# decoupling.net
KiCad netlist of a schematic drawn in Altium Designer
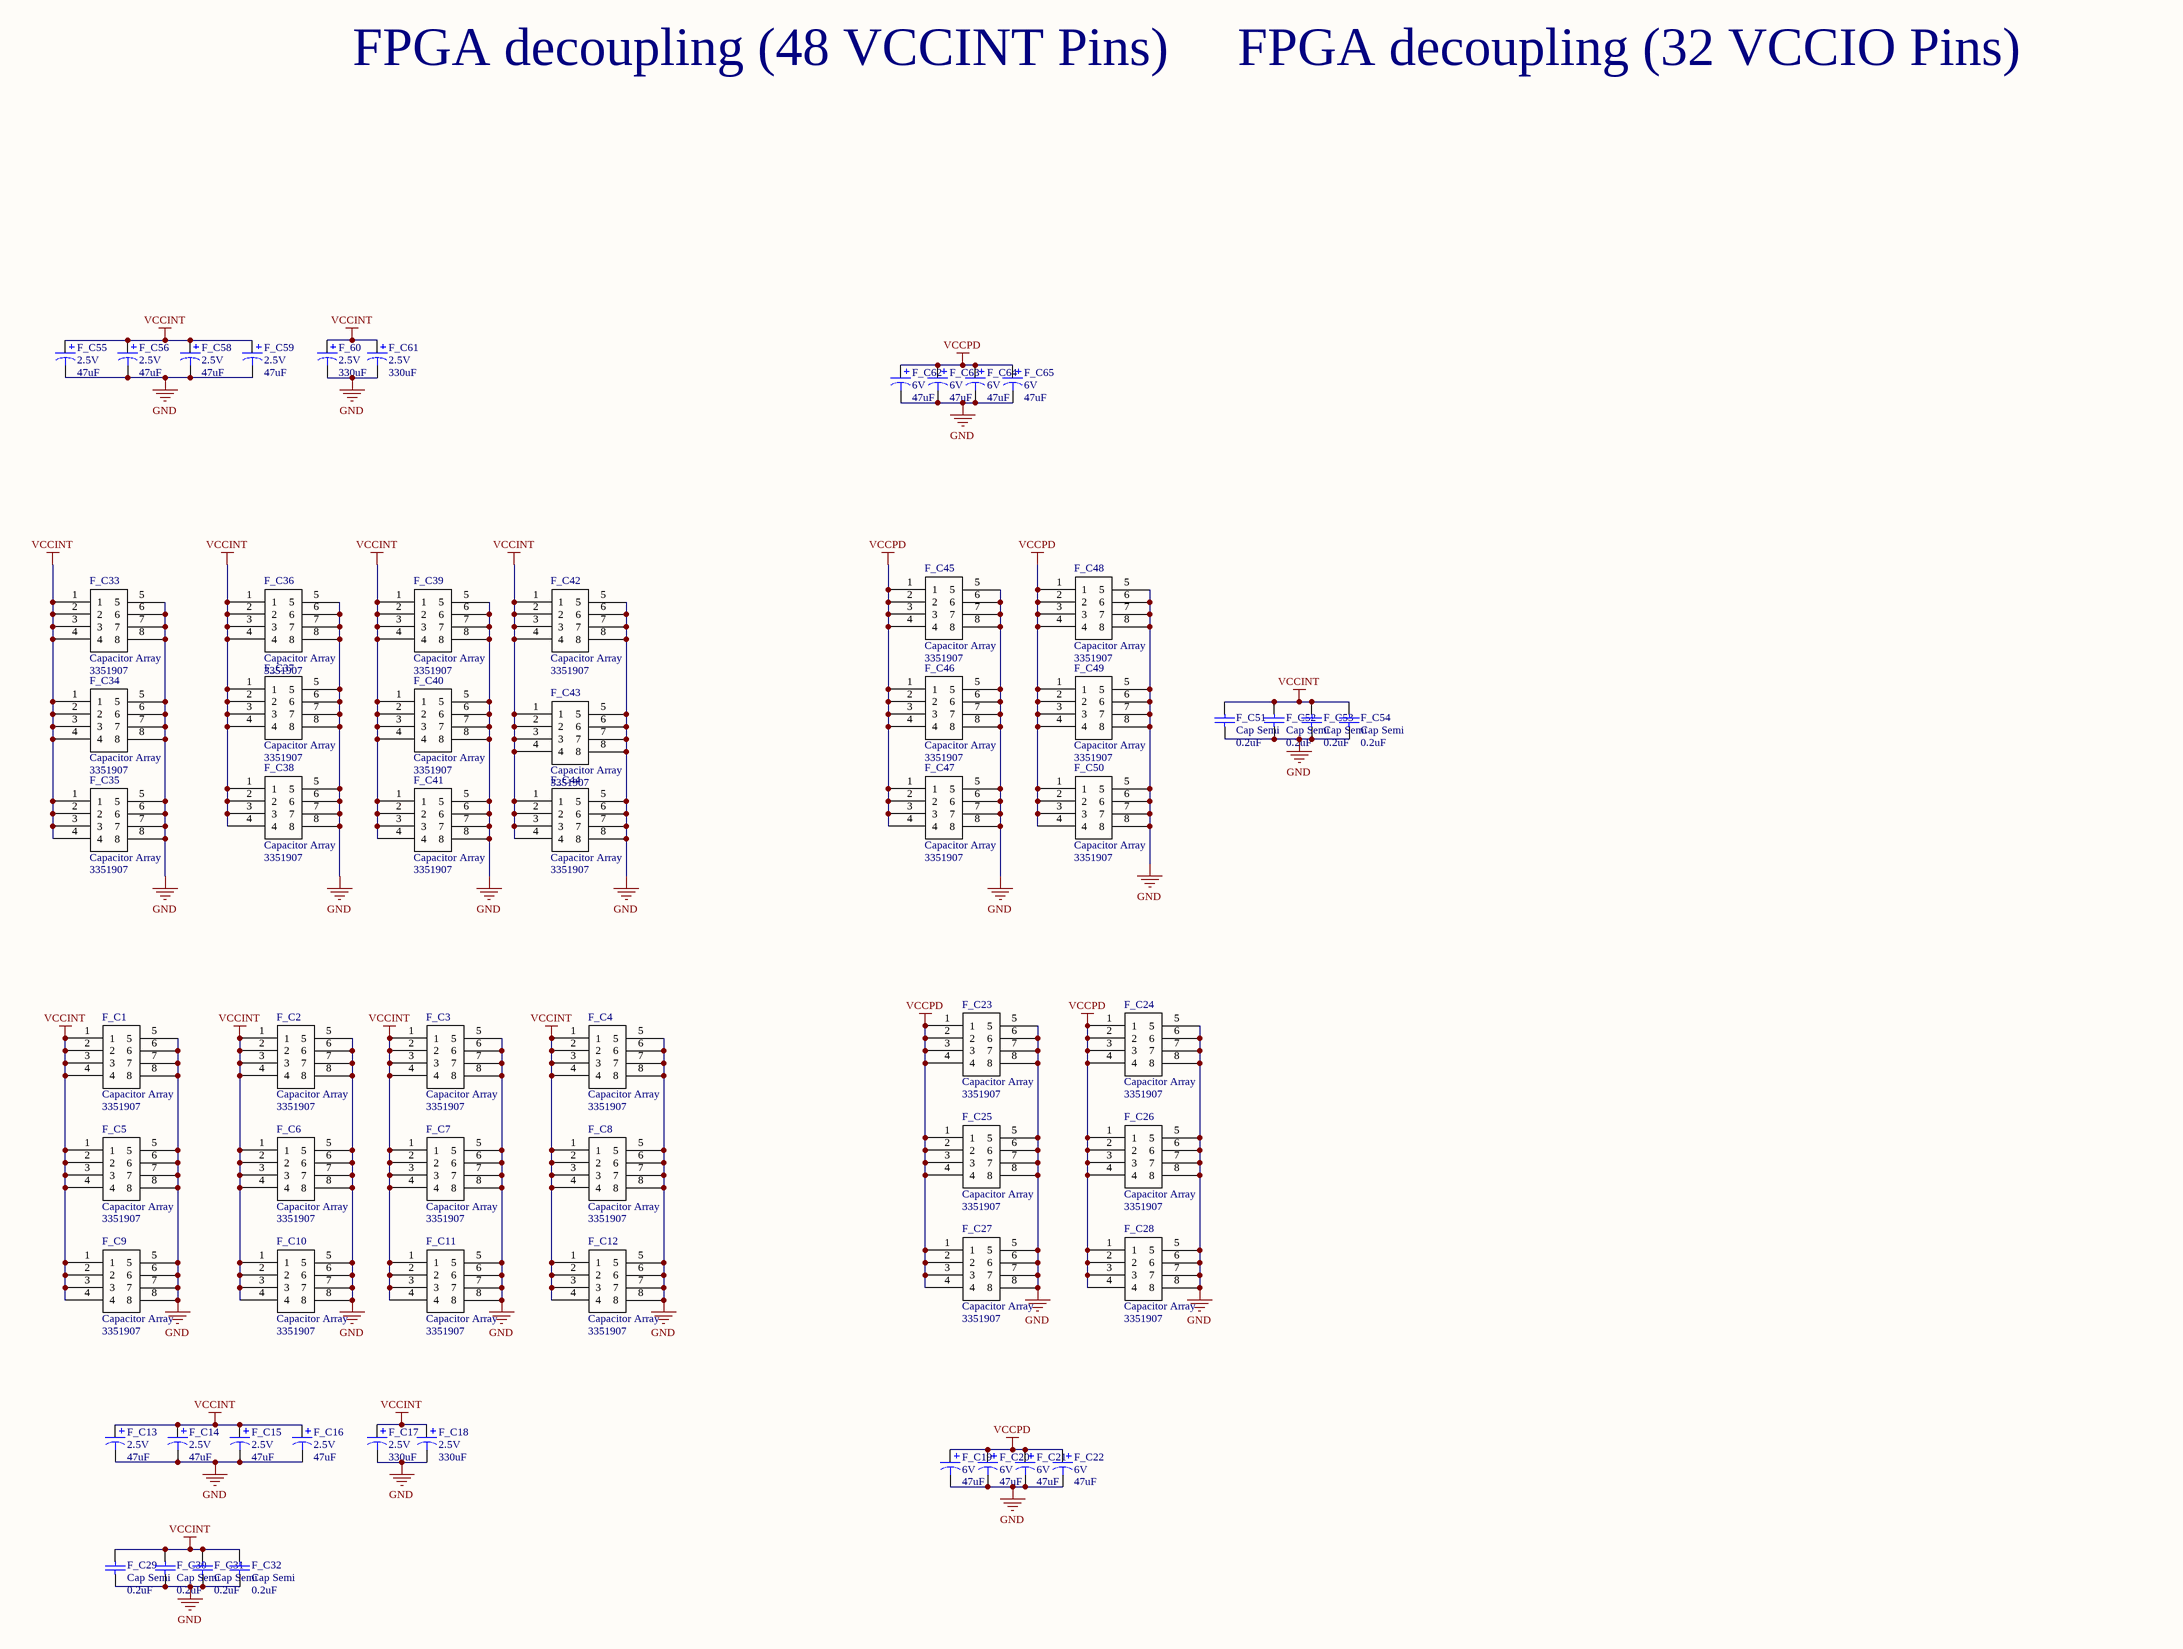
[diagram p0: decoupling.SchDoc]

(export (version "E")
  (design (tool "Eeschema 10.0.6"))
  (components
    (comp (ref "F_60")
      (value "2.5V")
      (footprint "E")
      (description "Polarized Capacitor (Surface Mount)")
      (fields (field (name "ALTIUM_VALUE") "330uF") (field (name "PUBLISHER") "Altium Limited"))
      (libsource (lib "Miscellaneous Devices") (part "Cap Pol3"))
    )
    (comp (ref "F_C1")
      (value "Capacitor Array")
      (footprint "0612 Array")
      (description "Array of 4x47nF")
      (fields (field (name "SUPPLIER PART NUMBER 1") "3351907"))
      (libsource (lib "Schematic Components") (part "Capacitor Array"))
    )
    (comp (ref "F_C2")
      (value "Capacitor Array")
      (footprint "0612 Array")
      (description "Array of 4x47nF")
      (fields (field (name "SUPPLIER PART NUMBER 1") "3351907"))
      (libsource (lib "Schematic Components") (part "Capacitor Array"))
    )
    (comp (ref "F_C3")
      (value "Capacitor Array")
      (footprint "0612 Array")
      (description "Array of 4x47nF")
      (fields (field (name "SUPPLIER PART NUMBER 1") "3351907"))
      (libsource (lib "Schematic Components") (part "Capacitor Array"))
    )
    (comp (ref "F_C4")
      (value "Capacitor Array")
      (footprint "0612 Array")
      (description "Array of 4x47nF")
      (fields (field (name "SUPPLIER PART NUMBER 1") "3351907"))
      (libsource (lib "Schematic Components") (part "Capacitor Array"))
    )
    (comp (ref "F_C5")
      (value "Capacitor Array")
      (footprint "0612 Array")
      (description "Array of 4x47nF")
      (fields (field (name "SUPPLIER PART NUMBER 1") "3351907"))
      (libsource (lib "Schematic Components") (part "Capacitor Array"))
    )
    (comp (ref "F_C6")
      (value "Capacitor Array")
      (footprint "0612 Array")
      (description "Array of 4x47nF")
      (fields (field (name "SUPPLIER PART NUMBER 1") "3351907"))
      (libsource (lib "Schematic Components") (part "Capacitor Array"))
    )
    (comp (ref "F_C7")
      (value "Capacitor Array")
      (footprint "0612 Array")
      (description "Array of 4x47nF")
      (fields (field (name "SUPPLIER PART NUMBER 1") "3351907"))
      (libsource (lib "Schematic Components") (part "Capacitor Array"))
    )
    (comp (ref "F_C8")
      (value "Capacitor Array")
      (footprint "0612 Array")
      (description "Array of 4x47nF")
      (fields (field (name "SUPPLIER PART NUMBER 1") "3351907"))
      (libsource (lib "Schematic Components") (part "Capacitor Array"))
    )
    (comp (ref "F_C9")
      (value "Capacitor Array")
      (footprint "0612 Array")
      (description "Array of 4x47nF")
      (fields (field (name "SUPPLIER PART NUMBER 1") "3351907"))
      (libsource (lib "Schematic Components") (part "Capacitor Array"))
    )
    (comp (ref "F_C10")
      (value "Capacitor Array")
      (footprint "0612 Array")
      (description "Array of 4x47nF")
      (fields (field (name "SUPPLIER PART NUMBER 1") "3351907"))
      (libsource (lib "Schematic Components") (part "Capacitor Array"))
    )
    (comp (ref "F_C11")
      (value "Capacitor Array")
      (footprint "0612 Array")
      (description "Array of 4x47nF")
      (fields (field (name "SUPPLIER PART NUMBER 1") "3351907"))
      (libsource (lib "Schematic Components") (part "Capacitor Array"))
    )
    (comp (ref "F_C12")
      (value "Capacitor Array")
      (footprint "0612 Array")
      (description "Array of 4x47nF")
      (fields (field (name "SUPPLIER PART NUMBER 1") "3351907"))
      (libsource (lib "Schematic Components") (part "Capacitor Array"))
    )
    (comp (ref "F_C13")
      (value "2.5V")
      (footprint "C")
      (description "Polarized Capacitor (Surface Mount)")
      (fields (field (name "ALTIUM_VALUE") "47uF") (field (name "PUBLISHER") "Altium Limited"))
      (libsource (lib "Miscellaneous Devices") (part "Cap Pol3"))
    )
    (comp (ref "F_C14")
      (value "2.5V")
      (footprint "C")
      (description "Polarized Capacitor (Surface Mount)")
      (fields (field (name "ALTIUM_VALUE") "47uF") (field (name "PUBLISHER") "Altium Limited"))
      (libsource (lib "Miscellaneous Devices") (part "Cap Pol3"))
    )
    (comp (ref "F_C15")
      (value "2.5V")
      (footprint "C")
      (description "Polarized Capacitor (Surface Mount)")
      (fields (field (name "ALTIUM_VALUE") "47uF") (field (name "PUBLISHER") "Altium Limited"))
      (libsource (lib "Miscellaneous Devices") (part "Cap Pol3"))
    )
    (comp (ref "F_C16")
      (value "2.5V")
      (footprint "C")
      (description "Polarized Capacitor (Surface Mount)")
      (fields (field (name "ALTIUM_VALUE") "47uF") (field (name "PUBLISHER") "Altium Limited"))
      (libsource (lib "Miscellaneous Devices") (part "Cap Pol3"))
    )
    (comp (ref "F_C17")
      (value "2.5V")
      (footprint "E")
      (description "Polarized Capacitor (Surface Mount)")
      (fields (field (name "ALTIUM_VALUE") "330uF") (field (name "PUBLISHER") "Altium Limited"))
      (libsource (lib "Miscellaneous Devices") (part "Cap Pol3"))
    )
    (comp (ref "F_C18")
      (value "2.5V")
      (footprint "E")
      (description "Polarized Capacitor (Surface Mount)")
      (fields (field (name "ALTIUM_VALUE") "330uF") (field (name "PUBLISHER") "Altium Limited"))
      (libsource (lib "Miscellaneous Devices") (part "Cap Pol3"))
    )
    (comp (ref "F_C19")
      (value "6V")
      (footprint "C")
      (description "Polarized Capacitor (Surface Mount)")
      (fields (field (name "ALTIUM_VALUE") "47uF") (field (name "PUBLISHER") "Altium Limited"))
      (libsource (lib "Miscellaneous Devices") (part "Cap Pol3"))
    )
    (comp (ref "F_C20")
      (value "6V")
      (footprint "C")
      (description "Polarized Capacitor (Surface Mount)")
      (fields (field (name "ALTIUM_VALUE") "47uF") (field (name "PUBLISHER") "Altium Limited"))
      (libsource (lib "Miscellaneous Devices") (part "Cap Pol3"))
    )
    (comp (ref "F_C21")
      (value "6V")
      (footprint "C")
      (description "Polarized Capacitor (Surface Mount)")
      (fields (field (name "ALTIUM_VALUE") "47uF") (field (name "PUBLISHER") "Altium Limited"))
      (libsource (lib "Miscellaneous Devices") (part "Cap Pol3"))
    )
    (comp (ref "F_C22")
      (value "6V")
      (footprint "C")
      (description "Polarized Capacitor (Surface Mount)")
      (fields (field (name "ALTIUM_VALUE") "47uF") (field (name "PUBLISHER") "Altium Limited"))
      (libsource (lib "Miscellaneous Devices") (part "Cap Pol3"))
    )
    (comp (ref "F_C23")
      (value "Capacitor Array")
      (footprint "0612 Array")
      (description "Array of 4x47nF")
      (fields (field (name "SUPPLIER PART NUMBER 1") "3351907"))
      (libsource (lib "Schematic Components") (part "Capacitor Array"))
    )
    (comp (ref "F_C24")
      (value "Capacitor Array")
      (footprint "0612 Array")
      (description "Array of 4x47nF")
      (fields (field (name "SUPPLIER PART NUMBER 1") "3351907"))
      (libsource (lib "Schematic Components") (part "Capacitor Array"))
    )
    (comp (ref "F_C25")
      (value "Capacitor Array")
      (footprint "0612 Array")
      (description "Array of 4x47nF")
      (fields (field (name "SUPPLIER PART NUMBER 1") "3351907"))
      (libsource (lib "Schematic Components") (part "Capacitor Array"))
    )
    (comp (ref "F_C26")
      (value "Capacitor Array")
      (footprint "0612 Array")
      (description "Array of 4x47nF")
      (fields (field (name "SUPPLIER PART NUMBER 1") "3351907"))
      (libsource (lib "Schematic Components") (part "Capacitor Array"))
    )
    (comp (ref "F_C27")
      (value "Capacitor Array")
      (footprint "0612 Array")
      (description "Array of 4x47nF")
      (fields (field (name "SUPPLIER PART NUMBER 1") "3351907"))
      (libsource (lib "Schematic Components") (part "Capacitor Array"))
    )
    (comp (ref "F_C28")
      (value "Capacitor Array")
      (footprint "0612 Array")
      (description "Array of 4x47nF")
      (fields (field (name "SUPPLIER PART NUMBER 1") "3351907"))
      (libsource (lib "Schematic Components") (part "Capacitor Array"))
    )
    (comp (ref "F_C29")
      (value "Cap Semi")
      (footprint "CAPC1608L")
      (description "Capacitor (Semiconductor SIM Model)")
      (fields (field (name "ALTIUM_VALUE") "0.2uF") (field (name "PUBLISHER") "Altium Limited"))
      (libsource (lib "Miscellaneous Devices") (part "Cap Semi"))
    )
    (comp (ref "F_C30")
      (value "Cap Semi")
      (footprint "CAPC1608L")
      (description "Capacitor (Semiconductor SIM Model)")
      (fields (field (name "ALTIUM_VALUE") "0.2uF") (field (name "PUBLISHER") "Altium Limited"))
      (libsource (lib "Miscellaneous Devices") (part "Cap Semi"))
    )
    (comp (ref "F_C31")
      (value "Cap Semi")
      (footprint "CAPC1608L")
      (description "Capacitor (Semiconductor SIM Model)")
      (fields (field (name "ALTIUM_VALUE") "0.2uF") (field (name "PUBLISHER") "Altium Limited"))
      (libsource (lib "Miscellaneous Devices") (part "Cap Semi"))
    )
    (comp (ref "F_C32")
      (value "Cap Semi")
      (footprint "CAPC1608L")
      (description "Capacitor (Semiconductor SIM Model)")
      (fields (field (name "ALTIUM_VALUE") "0.2uF") (field (name "PUBLISHER") "Altium Limited"))
      (libsource (lib "Miscellaneous Devices") (part "Cap Semi"))
    )
    (comp (ref "F_C33")
      (value "Capacitor Array")
      (footprint "0612 Array")
      (fields (field (name "SUPPLIER PART NUMBER 1") "3351907"))
      (libsource (lib "Schematic Components") (part "Capacitor Array"))
    )
    (comp (ref "F_C34")
      (value "Capacitor Array")
      (footprint "0612 Array")
      (fields (field (name "SUPPLIER PART NUMBER 1") "3351907"))
      (libsource (lib "Schematic Components") (part "Capacitor Array"))
    )
    (comp (ref "F_C35")
      (value "Capacitor Array")
      (footprint "0612 Array")
      (fields (field (name "SUPPLIER PART NUMBER 1") "3351907"))
      (libsource (lib "Schematic Components") (part "Capacitor Array"))
    )
    (comp (ref "F_C36")
      (value "Capacitor Array")
      (footprint "0612 Array")
      (fields (field (name "SUPPLIER PART NUMBER 1") "3351907"))
      (libsource (lib "Schematic Components") (part "Capacitor Array"))
    )
    (comp (ref "F_C37")
      (value "Capacitor Array")
      (footprint "0612 Array")
      (fields (field (name "SUPPLIER PART NUMBER 1") "3351907"))
      (libsource (lib "Schematic Components") (part "Capacitor Array"))
    )
    (comp (ref "F_C38")
      (value "Capacitor Array")
      (footprint "0612 Array")
      (fields (field (name "SUPPLIER PART NUMBER 1") "3351907"))
      (libsource (lib "Schematic Components") (part "Capacitor Array"))
    )
    (comp (ref "F_C39")
      (value "Capacitor Array")
      (footprint "0612 Array")
      (fields (field (name "SUPPLIER PART NUMBER 1") "3351907"))
      (libsource (lib "Schematic Components") (part "Capacitor Array"))
    )
    (comp (ref "F_C40")
      (value "Capacitor Array")
      (footprint "0612 Array")
      (fields (field (name "SUPPLIER PART NUMBER 1") "3351907"))
      (libsource (lib "Schematic Components") (part "Capacitor Array"))
    )
    (comp (ref "F_C41")
      (value "Capacitor Array")
      (footprint "0612 Array")
      (fields (field (name "SUPPLIER PART NUMBER 1") "3351907"))
      (libsource (lib "Schematic Components") (part "Capacitor Array"))
    )
    (comp (ref "F_C42")
      (value "Capacitor Array")
      (footprint "0612 Array")
      (fields (field (name "SUPPLIER PART NUMBER 1") "3351907"))
      (libsource (lib "Schematic Components") (part "Capacitor Array"))
    )
    (comp (ref "F_C43")
      (value "Capacitor Array")
      (footprint "0612 Array")
      (fields (field (name "SUPPLIER PART NUMBER 1") "3351907"))
      (libsource (lib "Schematic Components") (part "Capacitor Array"))
    )
    (comp (ref "F_C44")
      (value "Capacitor Array")
      (footprint "0612 Array")
      (fields (field (name "SUPPLIER PART NUMBER 1") "3351907"))
      (libsource (lib "Schematic Components") (part "Capacitor Array"))
    )
    (comp (ref "F_C45")
      (value "Capacitor Array")
      (footprint "0612 Array")
      (fields (field (name "SUPPLIER PART NUMBER 1") "3351907"))
      (libsource (lib "Schematic Components") (part "Capacitor Array"))
    )
    (comp (ref "F_C46")
      (value "Capacitor Array")
      (footprint "0612 Array")
      (fields (field (name "SUPPLIER PART NUMBER 1") "3351907"))
      (libsource (lib "Schematic Components") (part "Capacitor Array"))
    )
    (comp (ref "F_C47")
      (value "Capacitor Array")
      (footprint "0612 Array")
      (fields (field (name "SUPPLIER PART NUMBER 1") "3351907"))
      (libsource (lib "Schematic Components") (part "Capacitor Array"))
    )
    (comp (ref "F_C48")
      (value "Capacitor Array")
      (footprint "0612 Array")
      (fields (field (name "SUPPLIER PART NUMBER 1") "3351907"))
      (libsource (lib "Schematic Components") (part "Capacitor Array"))
    )
    (comp (ref "F_C49")
      (value "Capacitor Array")
      (footprint "0612 Array")
      (fields (field (name "SUPPLIER PART NUMBER 1") "3351907"))
      (libsource (lib "Schematic Components") (part "Capacitor Array"))
    )
    (comp (ref "F_C50")
      (value "Capacitor Array")
      (footprint "0612 Array")
      (fields (field (name "SUPPLIER PART NUMBER 1") "3351907"))
      (libsource (lib "Schematic Components") (part "Capacitor Array"))
    )
    (comp (ref "F_C51")
      (value "Cap Semi")
      (footprint "CAPC1608L")
      (description "Capacitor (Semiconductor SIM Model)")
      (fields (field (name "ALTIUM_VALUE") "0.2uF") (field (name "PUBLISHER") "Altium Limited"))
      (libsource (lib "Miscellaneous Devices") (part "Cap Semi"))
    )
    (comp (ref "F_C52")
      (value "Cap Semi")
      (footprint "CAPC1608L")
      (description "Capacitor (Semiconductor SIM Model)")
      (fields (field (name "ALTIUM_VALUE") "0.2uF") (field (name "PUBLISHER") "Altium Limited"))
      (libsource (lib "Miscellaneous Devices") (part "Cap Semi"))
    )
    (comp (ref "F_C53")
      (value "Cap Semi")
      (footprint "CAPC1608L")
      (description "Capacitor (Semiconductor SIM Model)")
      (fields (field (name "ALTIUM_VALUE") "0.2uF") (field (name "PUBLISHER") "Altium Limited"))
      (libsource (lib "Miscellaneous Devices") (part "Cap Semi"))
    )
    (comp (ref "F_C54")
      (value "Cap Semi")
      (footprint "CAPC1608L")
      (description "Capacitor (Semiconductor SIM Model)")
      (fields (field (name "ALTIUM_VALUE") "0.2uF") (field (name "PUBLISHER") "Altium Limited"))
      (libsource (lib "Miscellaneous Devices") (part "Cap Semi"))
    )
    (comp (ref "F_C55")
      (value "2.5V")
      (footprint "C")
      (description "Polarized Capacitor (Surface Mount)")
      (fields (field (name "ALTIUM_VALUE") "47uF") (field (name "PUBLISHER") "Altium Limited"))
      (libsource (lib "Miscellaneous Devices") (part "Cap Pol3"))
    )
    (comp (ref "F_C56")
      (value "2.5V")
      (footprint "C")
      (description "Polarized Capacitor (Surface Mount)")
      (fields (field (name "ALTIUM_VALUE") "47uF") (field (name "PUBLISHER") "Altium Limited"))
      (libsource (lib "Miscellaneous Devices") (part "Cap Pol3"))
    )
    (comp (ref "F_C58")
      (value "2.5V")
      (footprint "C")
      (description "Polarized Capacitor (Surface Mount)")
      (fields (field (name "ALTIUM_VALUE") "47uF") (field (name "PUBLISHER") "Altium Limited"))
      (libsource (lib "Miscellaneous Devices") (part "Cap Pol3"))
    )
    (comp (ref "F_C59")
      (value "2.5V")
      (footprint "C")
      (description "Polarized Capacitor (Surface Mount)")
      (fields (field (name "ALTIUM_VALUE") "47uF") (field (name "PUBLISHER") "Altium Limited"))
      (libsource (lib "Miscellaneous Devices") (part "Cap Pol3"))
    )
    (comp (ref "F_C61")
      (value "2.5V")
      (footprint "E")
      (description "Polarized Capacitor (Surface Mount)")
      (fields (field (name "ALTIUM_VALUE") "330uF") (field (name "PUBLISHER") "Altium Limited"))
      (libsource (lib "Miscellaneous Devices") (part "Cap Pol3"))
    )
    (comp (ref "F_C62")
      (value "6V")
      (footprint "C")
      (description "Polarized Capacitor (Surface Mount)")
      (fields (field (name "ALTIUM_VALUE") "47uF") (field (name "PUBLISHER") "Altium Limited"))
      (libsource (lib "Miscellaneous Devices") (part "Cap Pol3"))
    )
    (comp (ref "F_C63")
      (value "6V")
      (footprint "C")
      (description "Polarized Capacitor (Surface Mount)")
      (fields (field (name "ALTIUM_VALUE") "47uF") (field (name "PUBLISHER") "Altium Limited"))
      (libsource (lib "Miscellaneous Devices") (part "Cap Pol3"))
    )
    (comp (ref "F_C64")
      (value "6V")
      (footprint "C")
      (description "Polarized Capacitor (Surface Mount)")
      (fields (field (name "ALTIUM_VALUE") "47uF") (field (name "PUBLISHER") "Altium Limited"))
      (libsource (lib "Miscellaneous Devices") (part "Cap Pol3"))
    )
    (comp (ref "F_C65")
      (value "6V")
      (footprint "C")
      (description "Polarized Capacitor (Surface Mount)")
      (fields (field (name "ALTIUM_VALUE") "47uF") (field (name "PUBLISHER") "Altium Limited"))
      (libsource (lib "Miscellaneous Devices") (part "Cap Pol3"))
    )
  )
  (nets
    (net (code "1") (name "GND") (class "Default")
      (node (ref "F_60") (pin "2") (pinfunction "2_2") (pintype "passive"))
      (node (ref "F_C1") (pin "5") (pinfunction "5_5") (pintype "power_in"))
      (node (ref "F_C1") (pin "6") (pinfunction "6_6") (pintype "power_in"))
      (node (ref "F_C1") (pin "7") (pinfunction "7_7") (pintype "power_in"))
      (node (ref "F_C1") (pin "8") (pinfunction "8_8") (pintype "power_in"))
      (node (ref "F_C10") (pin "5") (pinfunction "5_5") (pintype "power_in"))
      (node (ref "F_C10") (pin "6") (pinfunction "6_6") (pintype "power_in"))
      (node (ref "F_C10") (pin "7") (pinfunction "7_7") (pintype "power_in"))
      (node (ref "F_C10") (pin "8") (pinfunction "8_8") (pintype "power_in"))
      (node (ref "F_C11") (pin "5") (pinfunction "5_5") (pintype "power_in"))
      (node (ref "F_C11") (pin "6") (pinfunction "6_6") (pintype "power_in"))
      (node (ref "F_C11") (pin "7") (pinfunction "7_7") (pintype "power_in"))
      (node (ref "F_C11") (pin "8") (pinfunction "8_8") (pintype "power_in"))
      (node (ref "F_C12") (pin "5") (pinfunction "5_5") (pintype "power_in"))
      (node (ref "F_C12") (pin "6") (pinfunction "6_6") (pintype "power_in"))
      (node (ref "F_C12") (pin "7") (pinfunction "7_7") (pintype "power_in"))
      (node (ref "F_C12") (pin "8") (pinfunction "8_8") (pintype "power_in"))
      (node (ref "F_C13") (pin "2") (pinfunction "2_2") (pintype "passive"))
      (node (ref "F_C14") (pin "2") (pinfunction "2_2") (pintype "passive"))
      (node (ref "F_C15") (pin "2") (pinfunction "2_2") (pintype "passive"))
      (node (ref "F_C16") (pin "2") (pinfunction "2_2") (pintype "passive"))
      (node (ref "F_C17") (pin "2") (pinfunction "2_2") (pintype "passive"))
      (node (ref "F_C18") (pin "2") (pinfunction "2_2") (pintype "passive"))
      (node (ref "F_C19") (pin "2") (pinfunction "2_2") (pintype "passive"))
      (node (ref "F_C2") (pin "5") (pinfunction "5_5") (pintype "power_in"))
      (node (ref "F_C2") (pin "6") (pinfunction "6_6") (pintype "power_in"))
      (node (ref "F_C2") (pin "7") (pinfunction "7_7") (pintype "power_in"))
      (node (ref "F_C2") (pin "8") (pinfunction "8_8") (pintype "power_in"))
      (node (ref "F_C20") (pin "2") (pinfunction "2_2") (pintype "passive"))
      (node (ref "F_C21") (pin "2") (pinfunction "2_2") (pintype "passive"))
      (node (ref "F_C22") (pin "2") (pinfunction "2_2") (pintype "passive"))
      (node (ref "F_C23") (pin "5") (pinfunction "5_5") (pintype "power_in"))
      (node (ref "F_C23") (pin "6") (pinfunction "6_6") (pintype "power_in"))
      (node (ref "F_C23") (pin "7") (pinfunction "7_7") (pintype "power_in"))
      (node (ref "F_C23") (pin "8") (pinfunction "8_8") (pintype "power_in"))
      (node (ref "F_C24") (pin "5") (pinfunction "5_5") (pintype "power_in"))
      (node (ref "F_C24") (pin "6") (pinfunction "6_6") (pintype "power_in"))
      (node (ref "F_C24") (pin "7") (pinfunction "7_7") (pintype "power_in"))
      (node (ref "F_C24") (pin "8") (pinfunction "8_8") (pintype "power_in"))
      (node (ref "F_C25") (pin "5") (pinfunction "5_5") (pintype "power_in"))
      (node (ref "F_C25") (pin "6") (pinfunction "6_6") (pintype "power_in"))
      (node (ref "F_C25") (pin "7") (pinfunction "7_7") (pintype "power_in"))
      (node (ref "F_C25") (pin "8") (pinfunction "8_8") (pintype "power_in"))
      (node (ref "F_C26") (pin "5") (pinfunction "5_5") (pintype "power_in"))
      (node (ref "F_C26") (pin "6") (pinfunction "6_6") (pintype "power_in"))
      (node (ref "F_C26") (pin "7") (pinfunction "7_7") (pintype "power_in"))
      (node (ref "F_C26") (pin "8") (pinfunction "8_8") (pintype "power_in"))
      (node (ref "F_C27") (pin "5") (pinfunction "5_5") (pintype "power_in"))
      (node (ref "F_C27") (pin "6") (pinfunction "6_6") (pintype "power_in"))
      (node (ref "F_C27") (pin "7") (pinfunction "7_7") (pintype "power_in"))
      (node (ref "F_C27") (pin "8") (pinfunction "8_8") (pintype "power_in"))
      (node (ref "F_C28") (pin "5") (pinfunction "5_5") (pintype "power_in"))
      (node (ref "F_C28") (pin "6") (pinfunction "6_6") (pintype "power_in"))
      (node (ref "F_C28") (pin "7") (pinfunction "7_7") (pintype "power_in"))
      (node (ref "F_C28") (pin "8") (pinfunction "8_8") (pintype "power_in"))
      (node (ref "F_C29") (pin "2") (pinfunction "2_2") (pintype "passive"))
      (node (ref "F_C3") (pin "5") (pinfunction "5_5") (pintype "power_in"))
      (node (ref "F_C3") (pin "6") (pinfunction "6_6") (pintype "power_in"))
      (node (ref "F_C3") (pin "7") (pinfunction "7_7") (pintype "power_in"))
      (node (ref "F_C3") (pin "8") (pinfunction "8_8") (pintype "power_in"))
      (node (ref "F_C30") (pin "2") (pinfunction "2_2") (pintype "passive"))
      (node (ref "F_C31") (pin "2") (pinfunction "2_2") (pintype "passive"))
      (node (ref "F_C32") (pin "2") (pinfunction "2_2") (pintype "passive"))
      (node (ref "F_C33") (pin "5") (pinfunction "5_5") (pintype "power_in"))
      (node (ref "F_C33") (pin "6") (pinfunction "6_6") (pintype "power_in"))
      (node (ref "F_C33") (pin "7") (pinfunction "7_7") (pintype "power_in"))
      (node (ref "F_C33") (pin "8") (pinfunction "8_8") (pintype "power_in"))
      (node (ref "F_C34") (pin "5") (pinfunction "5_5") (pintype "power_in"))
      (node (ref "F_C34") (pin "6") (pinfunction "6_6") (pintype "power_in"))
      (node (ref "F_C34") (pin "7") (pinfunction "7_7") (pintype "power_in"))
      (node (ref "F_C34") (pin "8") (pinfunction "8_8") (pintype "power_in"))
      (node (ref "F_C35") (pin "5") (pinfunction "5_5") (pintype "power_in"))
      (node (ref "F_C35") (pin "6") (pinfunction "6_6") (pintype "power_in"))
      (node (ref "F_C35") (pin "7") (pinfunction "7_7") (pintype "power_in"))
      (node (ref "F_C35") (pin "8") (pinfunction "8_8") (pintype "power_in"))
      (node (ref "F_C36") (pin "5") (pinfunction "5_5") (pintype "power_in"))
      (node (ref "F_C36") (pin "6") (pinfunction "6_6") (pintype "power_in"))
      (node (ref "F_C36") (pin "7") (pinfunction "7_7") (pintype "power_in"))
      (node (ref "F_C36") (pin "8") (pinfunction "8_8") (pintype "power_in"))
      (node (ref "F_C37") (pin "5") (pinfunction "5_5") (pintype "power_in"))
      (node (ref "F_C37") (pin "6") (pinfunction "6_6") (pintype "power_in"))
      (node (ref "F_C37") (pin "7") (pinfunction "7_7") (pintype "power_in"))
      (node (ref "F_C37") (pin "8") (pinfunction "8_8") (pintype "power_in"))
      (node (ref "F_C38") (pin "5") (pinfunction "5_5") (pintype "power_in"))
      (node (ref "F_C38") (pin "6") (pinfunction "6_6") (pintype "power_in"))
      (node (ref "F_C38") (pin "7") (pinfunction "7_7") (pintype "power_in"))
      (node (ref "F_C38") (pin "8") (pinfunction "8_8") (pintype "power_in"))
      (node (ref "F_C39") (pin "5") (pinfunction "5_5") (pintype "power_in"))
      (node (ref "F_C39") (pin "6") (pinfunction "6_6") (pintype "power_in"))
      (node (ref "F_C39") (pin "7") (pinfunction "7_7") (pintype "power_in"))
      (node (ref "F_C39") (pin "8") (pinfunction "8_8") (pintype "power_in"))
      (node (ref "F_C4") (pin "5") (pinfunction "5_5") (pintype "power_in"))
      (node (ref "F_C4") (pin "6") (pinfunction "6_6") (pintype "power_in"))
      (node (ref "F_C4") (pin "7") (pinfunction "7_7") (pintype "power_in"))
      (node (ref "F_C4") (pin "8") (pinfunction "8_8") (pintype "power_in"))
      (node (ref "F_C40") (pin "5") (pinfunction "5_5") (pintype "power_in"))
      (node (ref "F_C40") (pin "6") (pinfunction "6_6") (pintype "power_in"))
      (node (ref "F_C40") (pin "7") (pinfunction "7_7") (pintype "power_in"))
      (node (ref "F_C40") (pin "8") (pinfunction "8_8") (pintype "power_in"))
      (node (ref "F_C41") (pin "5") (pinfunction "5_5") (pintype "power_in"))
      (node (ref "F_C41") (pin "6") (pinfunction "6_6") (pintype "power_in"))
      (node (ref "F_C41") (pin "7") (pinfunction "7_7") (pintype "power_in"))
      (node (ref "F_C41") (pin "8") (pinfunction "8_8") (pintype "power_in"))
      (node (ref "F_C42") (pin "5") (pinfunction "5_5") (pintype "power_in"))
      (node (ref "F_C42") (pin "6") (pinfunction "6_6") (pintype "power_in"))
      (node (ref "F_C42") (pin "7") (pinfunction "7_7") (pintype "power_in"))
      (node (ref "F_C42") (pin "8") (pinfunction "8_8") (pintype "power_in"))
      (node (ref "F_C43") (pin "5") (pinfunction "5_5") (pintype "power_in"))
      (node (ref "F_C43") (pin "6") (pinfunction "6_6") (pintype "power_in"))
      (node (ref "F_C43") (pin "7") (pinfunction "7_7") (pintype "power_in"))
      (node (ref "F_C43") (pin "8") (pinfunction "8_8") (pintype "power_in"))
      (node (ref "F_C44") (pin "5") (pinfunction "5_5") (pintype "power_in"))
      (node (ref "F_C44") (pin "6") (pinfunction "6_6") (pintype "power_in"))
      (node (ref "F_C44") (pin "7") (pinfunction "7_7") (pintype "power_in"))
      (node (ref "F_C44") (pin "8") (pinfunction "8_8") (pintype "power_in"))
      (node (ref "F_C45") (pin "5") (pinfunction "5_5") (pintype "power_in"))
      (node (ref "F_C45") (pin "6") (pinfunction "6_6") (pintype "power_in"))
      (node (ref "F_C45") (pin "7") (pinfunction "7_7") (pintype "power_in"))
      (node (ref "F_C45") (pin "8") (pinfunction "8_8") (pintype "power_in"))
      (node (ref "F_C46") (pin "5") (pinfunction "5_5") (pintype "power_in"))
      (node (ref "F_C46") (pin "6") (pinfunction "6_6") (pintype "power_in"))
      (node (ref "F_C46") (pin "7") (pinfunction "7_7") (pintype "power_in"))
      (node (ref "F_C46") (pin "8") (pinfunction "8_8") (pintype "power_in"))
      (node (ref "F_C47") (pin "5") (pinfunction "5_5") (pintype "power_in"))
      (node (ref "F_C47") (pin "6") (pinfunction "6_6") (pintype "power_in"))
      (node (ref "F_C47") (pin "7") (pinfunction "7_7") (pintype "power_in"))
      (node (ref "F_C47") (pin "8") (pinfunction "8_8") (pintype "power_in"))
      (node (ref "F_C48") (pin "5") (pinfunction "5_5") (pintype "power_in"))
      (node (ref "F_C48") (pin "6") (pinfunction "6_6") (pintype "power_in"))
      (node (ref "F_C48") (pin "7") (pinfunction "7_7") (pintype "power_in"))
      (node (ref "F_C48") (pin "8") (pinfunction "8_8") (pintype "power_in"))
      (node (ref "F_C49") (pin "5") (pinfunction "5_5") (pintype "power_in"))
      (node (ref "F_C49") (pin "6") (pinfunction "6_6") (pintype "power_in"))
      (node (ref "F_C49") (pin "7") (pinfunction "7_7") (pintype "power_in"))
      (node (ref "F_C49") (pin "8") (pinfunction "8_8") (pintype "power_in"))
      (node (ref "F_C5") (pin "5") (pinfunction "5_5") (pintype "power_in"))
      (node (ref "F_C5") (pin "6") (pinfunction "6_6") (pintype "power_in"))
      (node (ref "F_C5") (pin "7") (pinfunction "7_7") (pintype "power_in"))
      (node (ref "F_C5") (pin "8") (pinfunction "8_8") (pintype "power_in"))
      (node (ref "F_C50") (pin "5") (pinfunction "5_5") (pintype "power_in"))
      (node (ref "F_C50") (pin "6") (pinfunction "6_6") (pintype "power_in"))
      (node (ref "F_C50") (pin "7") (pinfunction "7_7") (pintype "power_in"))
      (node (ref "F_C50") (pin "8") (pinfunction "8_8") (pintype "power_in"))
      (node (ref "F_C51") (pin "2") (pinfunction "2_2") (pintype "passive"))
      (node (ref "F_C52") (pin "2") (pinfunction "2_2") (pintype "passive"))
      (node (ref "F_C53") (pin "2") (pinfunction "2_2") (pintype "passive"))
      (node (ref "F_C54") (pin "2") (pinfunction "2_2") (pintype "passive"))
      (node (ref "F_C55") (pin "2") (pinfunction "2_2") (pintype "passive"))
      (node (ref "F_C56") (pin "2") (pinfunction "2_2") (pintype "passive"))
      (node (ref "F_C58") (pin "2") (pinfunction "2_2") (pintype "passive"))
      (node (ref "F_C59") (pin "2") (pinfunction "2_2") (pintype "passive"))
      (node (ref "F_C6") (pin "5") (pinfunction "5_5") (pintype "power_in"))
      (node (ref "F_C6") (pin "6") (pinfunction "6_6") (pintype "power_in"))
      (node (ref "F_C6") (pin "7") (pinfunction "7_7") (pintype "power_in"))
      (node (ref "F_C6") (pin "8") (pinfunction "8_8") (pintype "power_in"))
      (node (ref "F_C61") (pin "2") (pinfunction "2_2") (pintype "passive"))
      (node (ref "F_C62") (pin "2") (pinfunction "2_2") (pintype "passive"))
      (node (ref "F_C63") (pin "2") (pinfunction "2_2") (pintype "passive"))
      (node (ref "F_C64") (pin "2") (pinfunction "2_2") (pintype "passive"))
      (node (ref "F_C65") (pin "2") (pinfunction "2_2") (pintype "passive"))
      (node (ref "F_C7") (pin "5") (pinfunction "5_5") (pintype "power_in"))
      (node (ref "F_C7") (pin "6") (pinfunction "6_6") (pintype "power_in"))
      (node (ref "F_C7") (pin "7") (pinfunction "7_7") (pintype "power_in"))
      (node (ref "F_C7") (pin "8") (pinfunction "8_8") (pintype "power_in"))
      (node (ref "F_C8") (pin "5") (pinfunction "5_5") (pintype "power_in"))
      (node (ref "F_C8") (pin "6") (pinfunction "6_6") (pintype "power_in"))
      (node (ref "F_C8") (pin "7") (pinfunction "7_7") (pintype "power_in"))
      (node (ref "F_C8") (pin "8") (pinfunction "8_8") (pintype "power_in"))
      (node (ref "F_C9") (pin "5") (pinfunction "5_5") (pintype "power_in"))
      (node (ref "F_C9") (pin "6") (pinfunction "6_6") (pintype "power_in"))
      (node (ref "F_C9") (pin "7") (pinfunction "7_7") (pintype "power_in"))
      (node (ref "F_C9") (pin "8") (pinfunction "8_8") (pintype "power_in"))
    )
    (net (code "2") (name "VCCINT") (class "Default")
      (node (ref "F_60") (pin "1") (pinfunction "1_1") (pintype "passive"))
      (node (ref "F_C1") (pin "1") (pinfunction "1_1") (pintype "power_in"))
      (node (ref "F_C1") (pin "2") (pinfunction "2_2") (pintype "power_in"))
      (node (ref "F_C1") (pin "3") (pinfunction "3_3") (pintype "power_in"))
      (node (ref "F_C1") (pin "4") (pinfunction "4_4") (pintype "power_in"))
      (node (ref "F_C10") (pin "1") (pinfunction "1_1") (pintype "power_in"))
      (node (ref "F_C10") (pin "2") (pinfunction "2_2") (pintype "power_in"))
      (node (ref "F_C10") (pin "3") (pinfunction "3_3") (pintype "power_in"))
      (node (ref "F_C10") (pin "4") (pinfunction "4_4") (pintype "power_in"))
      (node (ref "F_C11") (pin "1") (pinfunction "1_1") (pintype "power_in"))
      (node (ref "F_C11") (pin "2") (pinfunction "2_2") (pintype "power_in"))
      (node (ref "F_C11") (pin "3") (pinfunction "3_3") (pintype "power_in"))
      (node (ref "F_C11") (pin "4") (pinfunction "4_4") (pintype "power_in"))
      (node (ref "F_C12") (pin "1") (pinfunction "1_1") (pintype "power_in"))
      (node (ref "F_C12") (pin "2") (pinfunction "2_2") (pintype "power_in"))
      (node (ref "F_C12") (pin "3") (pinfunction "3_3") (pintype "power_in"))
      (node (ref "F_C12") (pin "4") (pinfunction "4_4") (pintype "power_in"))
      (node (ref "F_C13") (pin "1") (pinfunction "1_1") (pintype "passive"))
      (node (ref "F_C14") (pin "1") (pinfunction "1_1") (pintype "passive"))
      (node (ref "F_C15") (pin "1") (pinfunction "1_1") (pintype "passive"))
      (node (ref "F_C16") (pin "1") (pinfunction "1_1") (pintype "passive"))
      (node (ref "F_C17") (pin "1") (pinfunction "1_1") (pintype "passive"))
      (node (ref "F_C18") (pin "1") (pinfunction "1_1") (pintype "passive"))
      (node (ref "F_C2") (pin "1") (pinfunction "1_1") (pintype "power_in"))
      (node (ref "F_C2") (pin "2") (pinfunction "2_2") (pintype "power_in"))
      (node (ref "F_C2") (pin "3") (pinfunction "3_3") (pintype "power_in"))
      (node (ref "F_C2") (pin "4") (pinfunction "4_4") (pintype "power_in"))
      (node (ref "F_C29") (pin "1") (pinfunction "1_1") (pintype "passive"))
      (node (ref "F_C3") (pin "1") (pinfunction "1_1") (pintype "power_in"))
      (node (ref "F_C3") (pin "2") (pinfunction "2_2") (pintype "power_in"))
      (node (ref "F_C3") (pin "3") (pinfunction "3_3") (pintype "power_in"))
      (node (ref "F_C3") (pin "4") (pinfunction "4_4") (pintype "power_in"))
      (node (ref "F_C30") (pin "1") (pinfunction "1_1") (pintype "passive"))
      (node (ref "F_C31") (pin "1") (pinfunction "1_1") (pintype "passive"))
      (node (ref "F_C32") (pin "1") (pinfunction "1_1") (pintype "passive"))
      (node (ref "F_C33") (pin "1") (pinfunction "1_1") (pintype "power_in"))
      (node (ref "F_C33") (pin "2") (pinfunction "2_2") (pintype "power_in"))
      (node (ref "F_C33") (pin "3") (pinfunction "3_3") (pintype "power_in"))
      (node (ref "F_C33") (pin "4") (pinfunction "4_4") (pintype "power_in"))
      (node (ref "F_C34") (pin "1") (pinfunction "1_1") (pintype "power_in"))
      (node (ref "F_C34") (pin "2") (pinfunction "2_2") (pintype "power_in"))
      (node (ref "F_C34") (pin "3") (pinfunction "3_3") (pintype "power_in"))
      (node (ref "F_C34") (pin "4") (pinfunction "4_4") (pintype "power_in"))
      (node (ref "F_C35") (pin "1") (pinfunction "1_1") (pintype "power_in"))
      (node (ref "F_C35") (pin "2") (pinfunction "2_2") (pintype "power_in"))
      (node (ref "F_C35") (pin "3") (pinfunction "3_3") (pintype "power_in"))
      (node (ref "F_C35") (pin "4") (pinfunction "4_4") (pintype "power_in"))
      (node (ref "F_C36") (pin "1") (pinfunction "1_1") (pintype "power_in"))
      (node (ref "F_C36") (pin "2") (pinfunction "2_2") (pintype "power_in"))
      (node (ref "F_C36") (pin "3") (pinfunction "3_3") (pintype "power_in"))
      (node (ref "F_C36") (pin "4") (pinfunction "4_4") (pintype "power_in"))
      (node (ref "F_C37") (pin "1") (pinfunction "1_1") (pintype "power_in"))
      (node (ref "F_C37") (pin "2") (pinfunction "2_2") (pintype "power_in"))
      (node (ref "F_C37") (pin "3") (pinfunction "3_3") (pintype "power_in"))
      (node (ref "F_C37") (pin "4") (pinfunction "4_4") (pintype "power_in"))
      (node (ref "F_C38") (pin "1") (pinfunction "1_1") (pintype "power_in"))
      (node (ref "F_C38") (pin "2") (pinfunction "2_2") (pintype "power_in"))
      (node (ref "F_C38") (pin "3") (pinfunction "3_3") (pintype "power_in"))
      (node (ref "F_C38") (pin "4") (pinfunction "4_4") (pintype "power_in"))
      (node (ref "F_C39") (pin "1") (pinfunction "1_1") (pintype "power_in"))
      (node (ref "F_C39") (pin "2") (pinfunction "2_2") (pintype "power_in"))
      (node (ref "F_C39") (pin "3") (pinfunction "3_3") (pintype "power_in"))
      (node (ref "F_C39") (pin "4") (pinfunction "4_4") (pintype "power_in"))
      (node (ref "F_C4") (pin "1") (pinfunction "1_1") (pintype "power_in"))
      (node (ref "F_C4") (pin "2") (pinfunction "2_2") (pintype "power_in"))
      (node (ref "F_C4") (pin "3") (pinfunction "3_3") (pintype "power_in"))
      (node (ref "F_C4") (pin "4") (pinfunction "4_4") (pintype "power_in"))
      (node (ref "F_C40") (pin "1") (pinfunction "1_1") (pintype "power_in"))
      (node (ref "F_C40") (pin "2") (pinfunction "2_2") (pintype "power_in"))
      (node (ref "F_C40") (pin "3") (pinfunction "3_3") (pintype "power_in"))
      (node (ref "F_C40") (pin "4") (pinfunction "4_4") (pintype "power_in"))
      (node (ref "F_C41") (pin "1") (pinfunction "1_1") (pintype "power_in"))
      (node (ref "F_C41") (pin "2") (pinfunction "2_2") (pintype "power_in"))
      (node (ref "F_C41") (pin "3") (pinfunction "3_3") (pintype "power_in"))
      (node (ref "F_C41") (pin "4") (pinfunction "4_4") (pintype "power_in"))
      (node (ref "F_C42") (pin "1") (pinfunction "1_1") (pintype "power_in"))
      (node (ref "F_C42") (pin "2") (pinfunction "2_2") (pintype "power_in"))
      (node (ref "F_C42") (pin "3") (pinfunction "3_3") (pintype "power_in"))
      (node (ref "F_C42") (pin "4") (pinfunction "4_4") (pintype "power_in"))
      (node (ref "F_C43") (pin "1") (pinfunction "1_1") (pintype "power_in"))
      (node (ref "F_C43") (pin "2") (pinfunction "2_2") (pintype "power_in"))
      (node (ref "F_C43") (pin "3") (pinfunction "3_3") (pintype "power_in"))
      (node (ref "F_C43") (pin "4") (pinfunction "4_4") (pintype "power_in"))
      (node (ref "F_C44") (pin "1") (pinfunction "1_1") (pintype "power_in"))
      (node (ref "F_C44") (pin "2") (pinfunction "2_2") (pintype "power_in"))
      (node (ref "F_C44") (pin "3") (pinfunction "3_3") (pintype "power_in"))
      (node (ref "F_C44") (pin "4") (pinfunction "4_4") (pintype "power_in"))
      (node (ref "F_C5") (pin "1") (pinfunction "1_1") (pintype "power_in"))
      (node (ref "F_C5") (pin "2") (pinfunction "2_2") (pintype "power_in"))
      (node (ref "F_C5") (pin "3") (pinfunction "3_3") (pintype "power_in"))
      (node (ref "F_C5") (pin "4") (pinfunction "4_4") (pintype "power_in"))
      (node (ref "F_C51") (pin "1") (pinfunction "1_1") (pintype "passive"))
      (node (ref "F_C52") (pin "1") (pinfunction "1_1") (pintype "passive"))
      (node (ref "F_C53") (pin "1") (pinfunction "1_1") (pintype "passive"))
      (node (ref "F_C54") (pin "1") (pinfunction "1_1") (pintype "passive"))
      (node (ref "F_C55") (pin "1") (pinfunction "1_1") (pintype "passive"))
      (node (ref "F_C56") (pin "1") (pinfunction "1_1") (pintype "passive"))
      (node (ref "F_C58") (pin "1") (pinfunction "1_1") (pintype "passive"))
      (node (ref "F_C59") (pin "1") (pinfunction "1_1") (pintype "passive"))
      (node (ref "F_C6") (pin "1") (pinfunction "1_1") (pintype "power_in"))
      (node (ref "F_C6") (pin "2") (pinfunction "2_2") (pintype "power_in"))
      (node (ref "F_C6") (pin "3") (pinfunction "3_3") (pintype "power_in"))
      (node (ref "F_C6") (pin "4") (pinfunction "4_4") (pintype "power_in"))
      (node (ref "F_C61") (pin "1") (pinfunction "1_1") (pintype "passive"))
      (node (ref "F_C7") (pin "1") (pinfunction "1_1") (pintype "power_in"))
      (node (ref "F_C7") (pin "2") (pinfunction "2_2") (pintype "power_in"))
      (node (ref "F_C7") (pin "3") (pinfunction "3_3") (pintype "power_in"))
      (node (ref "F_C7") (pin "4") (pinfunction "4_4") (pintype "power_in"))
      (node (ref "F_C8") (pin "1") (pinfunction "1_1") (pintype "power_in"))
      (node (ref "F_C8") (pin "2") (pinfunction "2_2") (pintype "power_in"))
      (node (ref "F_C8") (pin "3") (pinfunction "3_3") (pintype "power_in"))
      (node (ref "F_C8") (pin "4") (pinfunction "4_4") (pintype "power_in"))
      (node (ref "F_C9") (pin "1") (pinfunction "1_1") (pintype "power_in"))
      (node (ref "F_C9") (pin "2") (pinfunction "2_2") (pintype "power_in"))
      (node (ref "F_C9") (pin "3") (pinfunction "3_3") (pintype "power_in"))
      (node (ref "F_C9") (pin "4") (pinfunction "4_4") (pintype "power_in"))
    )
    (net (code "3") (name "VCCPD") (class "Default")
      (node (ref "F_C19") (pin "1") (pinfunction "1_1") (pintype "passive"))
      (node (ref "F_C20") (pin "1") (pinfunction "1_1") (pintype "passive"))
      (node (ref "F_C21") (pin "1") (pinfunction "1_1") (pintype "passive"))
      (node (ref "F_C22") (pin "1") (pinfunction "1_1") (pintype "passive"))
      (node (ref "F_C23") (pin "1") (pinfunction "1_1") (pintype "power_in"))
      (node (ref "F_C23") (pin "2") (pinfunction "2_2") (pintype "power_in"))
      (node (ref "F_C23") (pin "3") (pinfunction "3_3") (pintype "power_in"))
      (node (ref "F_C23") (pin "4") (pinfunction "4_4") (pintype "power_in"))
      (node (ref "F_C24") (pin "1") (pinfunction "1_1") (pintype "power_in"))
      (node (ref "F_C24") (pin "2") (pinfunction "2_2") (pintype "power_in"))
      (node (ref "F_C24") (pin "3") (pinfunction "3_3") (pintype "power_in"))
      (node (ref "F_C24") (pin "4") (pinfunction "4_4") (pintype "power_in"))
      (node (ref "F_C25") (pin "1") (pinfunction "1_1") (pintype "power_in"))
      (node (ref "F_C25") (pin "2") (pinfunction "2_2") (pintype "power_in"))
      (node (ref "F_C25") (pin "3") (pinfunction "3_3") (pintype "power_in"))
      (node (ref "F_C25") (pin "4") (pinfunction "4_4") (pintype "power_in"))
      (node (ref "F_C26") (pin "1") (pinfunction "1_1") (pintype "power_in"))
      (node (ref "F_C26") (pin "2") (pinfunction "2_2") (pintype "power_in"))
      (node (ref "F_C26") (pin "3") (pinfunction "3_3") (pintype "power_in"))
      (node (ref "F_C26") (pin "4") (pinfunction "4_4") (pintype "power_in"))
      (node (ref "F_C27") (pin "1") (pinfunction "1_1") (pintype "power_in"))
      (node (ref "F_C27") (pin "2") (pinfunction "2_2") (pintype "power_in"))
      (node (ref "F_C27") (pin "3") (pinfunction "3_3") (pintype "power_in"))
      (node (ref "F_C27") (pin "4") (pinfunction "4_4") (pintype "power_in"))
      (node (ref "F_C28") (pin "1") (pinfunction "1_1") (pintype "power_in"))
      (node (ref "F_C28") (pin "2") (pinfunction "2_2") (pintype "power_in"))
      (node (ref "F_C28") (pin "3") (pinfunction "3_3") (pintype "power_in"))
      (node (ref "F_C28") (pin "4") (pinfunction "4_4") (pintype "power_in"))
      (node (ref "F_C45") (pin "1") (pinfunction "1_1") (pintype "power_in"))
      (node (ref "F_C45") (pin "2") (pinfunction "2_2") (pintype "power_in"))
      (node (ref "F_C45") (pin "3") (pinfunction "3_3") (pintype "power_in"))
      (node (ref "F_C45") (pin "4") (pinfunction "4_4") (pintype "power_in"))
      (node (ref "F_C46") (pin "1") (pinfunction "1_1") (pintype "power_in"))
      (node (ref "F_C46") (pin "2") (pinfunction "2_2") (pintype "power_in"))
      (node (ref "F_C46") (pin "3") (pinfunction "3_3") (pintype "power_in"))
      (node (ref "F_C46") (pin "4") (pinfunction "4_4") (pintype "power_in"))
      (node (ref "F_C47") (pin "1") (pinfunction "1_1") (pintype "power_in"))
      (node (ref "F_C47") (pin "2") (pinfunction "2_2") (pintype "power_in"))
      (node (ref "F_C47") (pin "3") (pinfunction "3_3") (pintype "power_in"))
      (node (ref "F_C47") (pin "4") (pinfunction "4_4") (pintype "power_in"))
      (node (ref "F_C48") (pin "1") (pinfunction "1_1") (pintype "power_in"))
      (node (ref "F_C48") (pin "2") (pinfunction "2_2") (pintype "power_in"))
      (node (ref "F_C48") (pin "3") (pinfunction "3_3") (pintype "power_in"))
      (node (ref "F_C48") (pin "4") (pinfunction "4_4") (pintype "power_in"))
      (node (ref "F_C49") (pin "1") (pinfunction "1_1") (pintype "power_in"))
      (node (ref "F_C49") (pin "2") (pinfunction "2_2") (pintype "power_in"))
      (node (ref "F_C49") (pin "3") (pinfunction "3_3") (pintype "power_in"))
      (node (ref "F_C49") (pin "4") (pinfunction "4_4") (pintype "power_in"))
      (node (ref "F_C50") (pin "1") (pinfunction "1_1") (pintype "power_in"))
      (node (ref "F_C50") (pin "2") (pinfunction "2_2") (pintype "power_in"))
      (node (ref "F_C50") (pin "3") (pinfunction "3_3") (pintype "power_in"))
      (node (ref "F_C50") (pin "4") (pinfunction "4_4") (pintype "power_in"))
      (node (ref "F_C62") (pin "1") (pinfunction "1_1") (pintype "passive"))
      (node (ref "F_C63") (pin "1") (pinfunction "1_1") (pintype "passive"))
      (node (ref "F_C64") (pin "1") (pinfunction "1_1") (pintype "passive"))
      (node (ref "F_C65") (pin "1") (pinfunction "1_1") (pintype "passive"))
    )
  )
)
